# Steering_Converter_1R1.net
KiCad netlist of a schematic drawn in Altium Designer
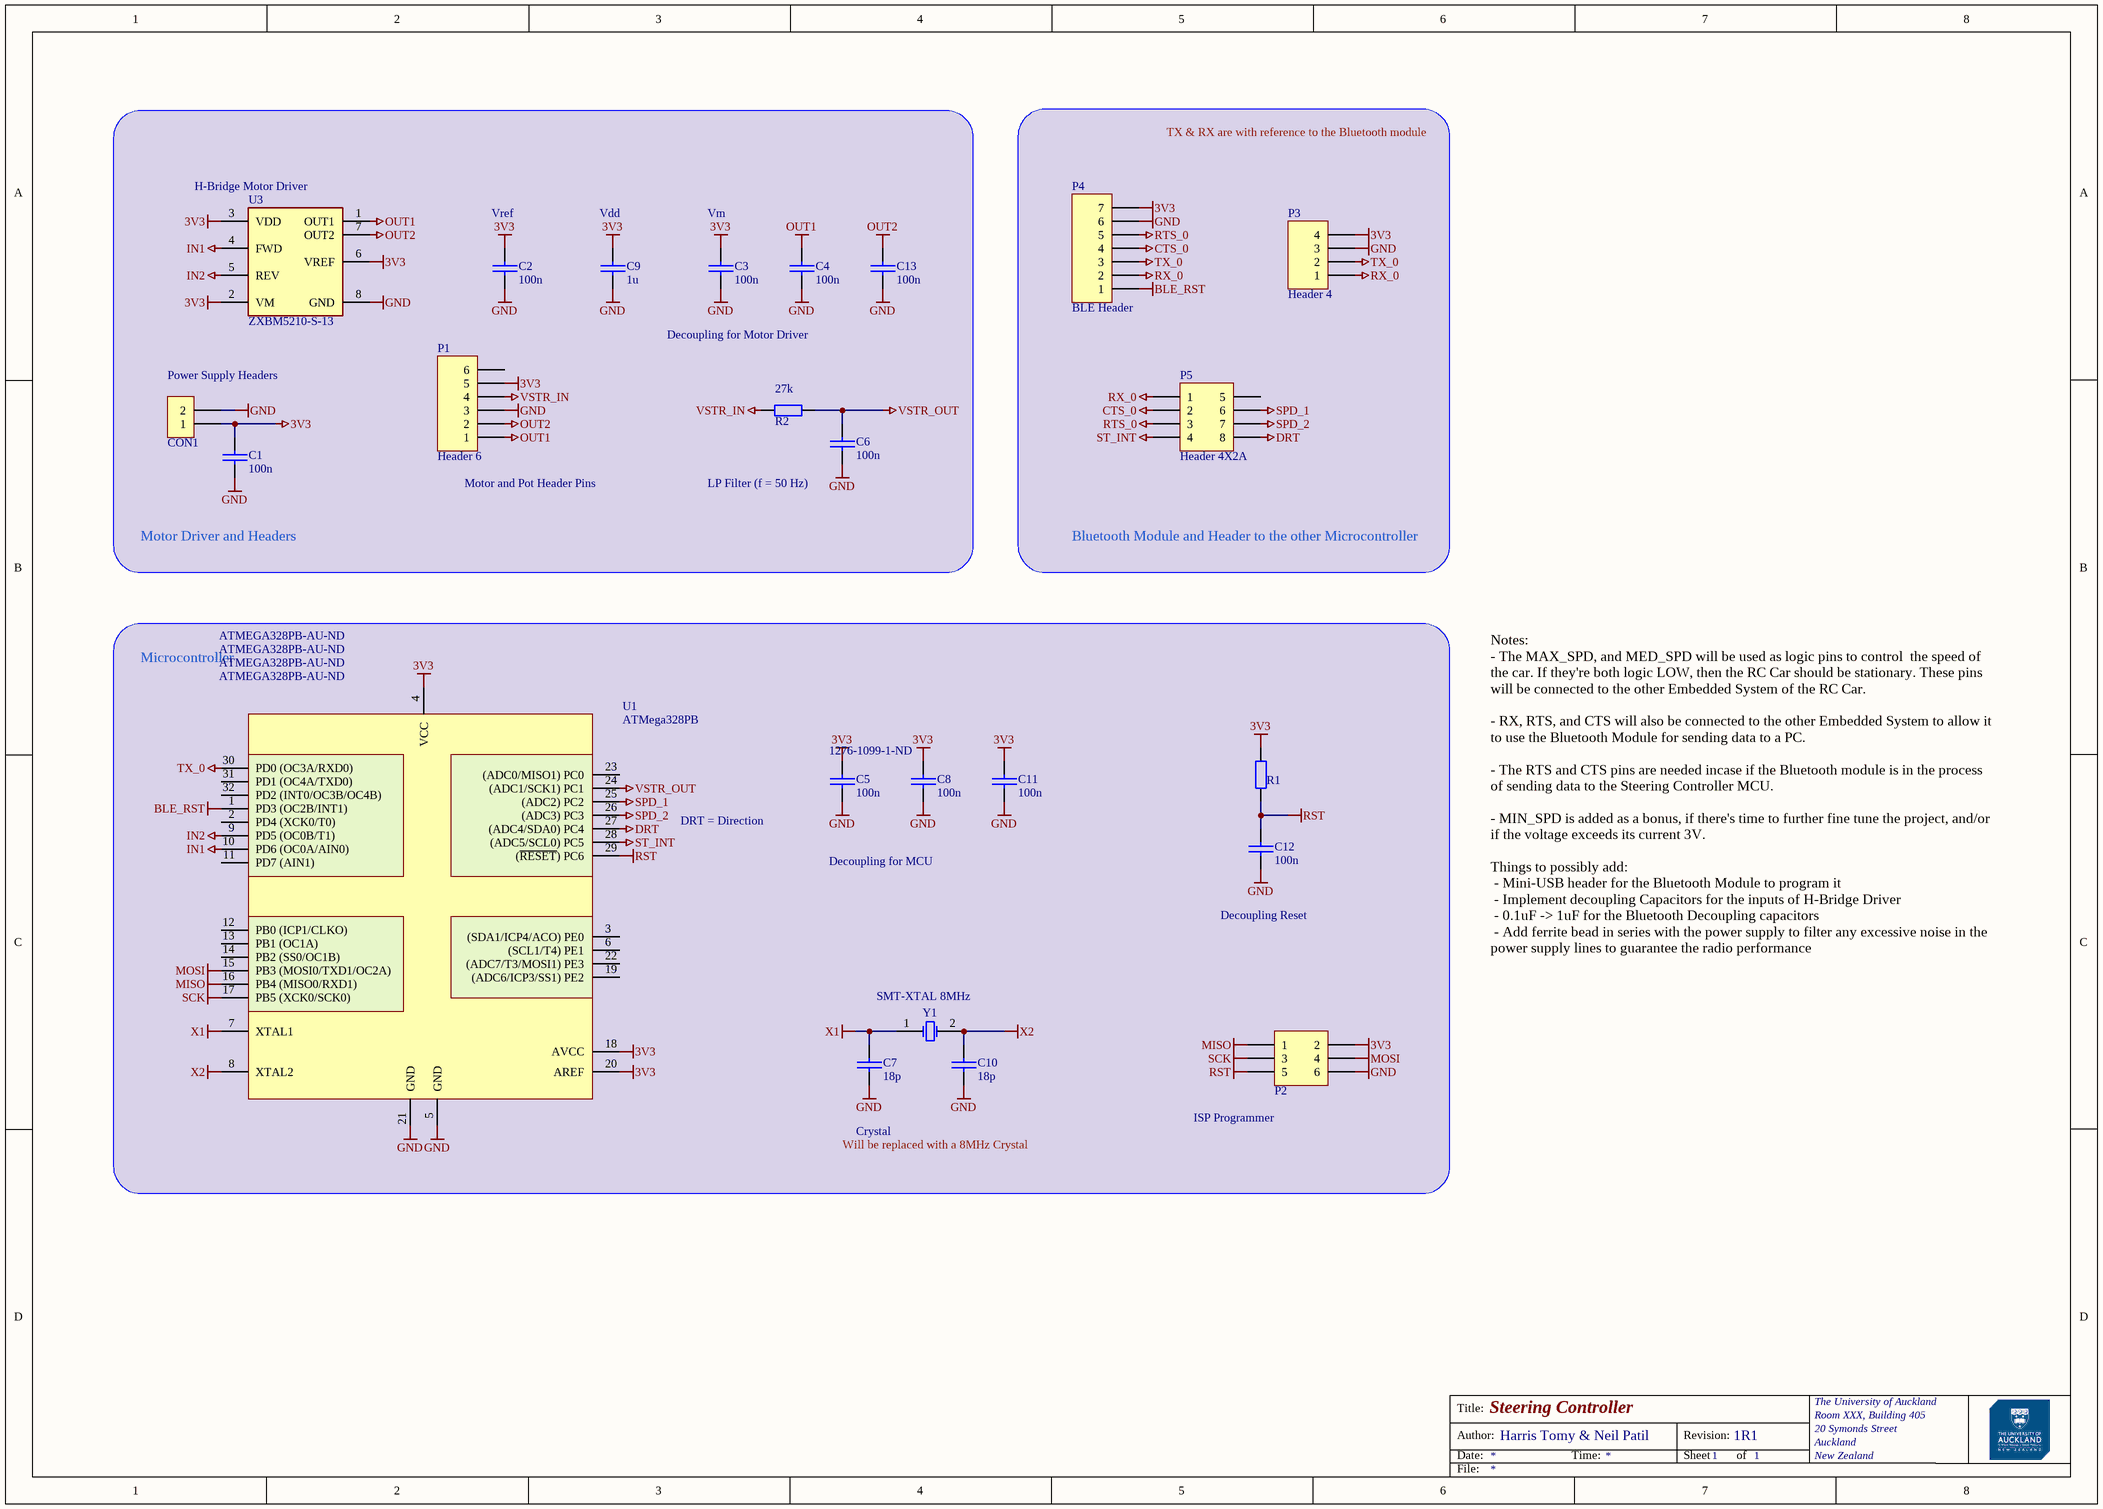
[diagram p0: Steering_Converter_1R1.SchDoc]

(export (version "E")
  (design (tool "Eeschema 10.0.6"))
  (components
    (comp (ref "C1")
      (value "100n")
      (footprint "C0805")
      (description "CCAP0805")
      (fields (field (name "MPN") "?"))
      (libsource (lib "E209_Lib") (part "CCAP0805"))
    )
    (comp (ref "C2")
      (value "100n")
      (footprint "C0805")
      (description "CCAP0805")
      (fields (field (name "MPN") "?"))
      (libsource (lib "E209_Lib") (part "CCAP0805"))
    )
    (comp (ref "C3")
      (value "100n")
      (footprint "C0805")
      (description "CCAP0805")
      (fields (field (name "MPN") "?"))
      (libsource (lib "E209_Lib") (part "CCAP0805"))
    )
    (comp (ref "C4")
      (value "100n")
      (footprint "C0805")
      (description "CCAP0805")
      (fields (field (name "MPN") "?"))
      (libsource (lib "E209_Lib") (part "CCAP0805"))
    )
    (comp (ref "C5")
      (value "100n")
      (footprint "C0805")
      (description "CCAP0805")
      (fields (field (name "MPN") "?") (field (name "SUPPLIER PART NUMBER 1") "1276-1099-1-ND"))
      (libsource (lib "E209_Lib") (part "CCAP0805"))
    )
    (comp (ref "C6")
      (value "100n")
      (footprint "C0805")
      (description "CCAP0805")
      (fields (field (name "MPN") "?"))
      (libsource (lib "E209_Lib") (part "CCAP0805"))
    )
    (comp (ref "C7")
      (value "18p")
      (footprint "C0805")
      (description "CCAP0805")
      (fields (field (name "MPN") "?"))
      (libsource (lib "E209_Lib") (part "CCAP0805"))
    )
    (comp (ref "C8")
      (value "100n")
      (footprint "C0805")
      (description "CCAP0805")
      (fields (field (name "MPN") "?"))
      (libsource (lib "E209_Lib") (part "CCAP0805"))
    )
    (comp (ref "C9")
      (value "1u")
      (footprint "C0805")
      (description "CCAP0805")
      (fields (field (name "MPN") "?"))
      (libsource (lib "E209_Lib") (part "CCAP0805"))
    )
    (comp (ref "C10")
      (value "18p")
      (footprint "C0805")
      (description "CCAP0805")
      (fields (field (name "MPN") "?"))
      (libsource (lib "E209_Lib") (part "CCAP0805"))
    )
    (comp (ref "C11")
      (value "100n")
      (footprint "C0805")
      (description "CCAP0805")
      (fields (field (name "MPN") "?"))
      (libsource (lib "E209_Lib") (part "CCAP0805"))
    )
    (comp (ref "C12")
      (value "100n")
      (footprint "C0805")
      (description "CCAP0805")
      (fields (field (name "MPN") "?"))
      (libsource (lib "E209_Lib") (part "CCAP0805"))
    )
    (comp (ref "C13")
      (value "100n")
      (footprint "C0805")
      (description "CCAP0805")
      (fields (field (name "MPN") "?"))
      (libsource (lib "E209_Lib") (part "CCAP0805"))
    )
    (comp (ref "CON1")
      (value "Header 2X1")
      (footprint "HDR2X1_2P54")
      (libsource (lib "CommonDevices_V1") (part "HDR2X1"))
    )
    (comp (ref "P1")
      (value "Header 6")
      (footprint "HDR1X6")
      (description "Header, 6-Pin")
      (fields (field (name "PUBLISHER") "Altium Limited"))
      (libsource (lib "Miscellaneous Connectors") (part "Header 6"))
    )
    (comp (ref "P2")
      (value "HDR3X2")
      (footprint "HDR2X3_2P54")
      (description "Header, 3-Pin, Dual row")
      (libsource (lib "CommonDevices_V1") (part "HDR3X2"))
    )
    (comp (ref "P3")
      (value "Header 4")
      (footprint "HDR1X4")
      (description "Header, 4-Pin")
      (fields (field (name "PUBLISHER") "Altium Limited"))
      (libsource (lib "Miscellaneous Connectors") (part "Header 4"))
    )
    (comp (ref "P4")
      (value "BLE Header")
      (footprint "HDR1X7")
      (description "Header, 7-Pin")
      (fields (field (name "PUBLISHER") "Altium Limited"))
      (libsource (lib "Miscellaneous Connectors") (part "Header 7"))
    )
    (comp (ref "P5")
      (value "Header 4X2A")
      (footprint "HDR2X4_CEN")
      (description "Header, 4-Pin, Dual row")
      (fields (field (name "PUBLISHER") "Altium Limited"))
      (libsource (lib "Miscellaneous Connectors") (part "Header 4X2A"))
    )
    (comp (ref "R1")
      (value "Resistor 0805")
      (footprint "R0805")
      (description "RES0805")
      (fields (field (name "MPN") "?"))
      (libsource (lib "E209_Lib") (part "RES0805"))
    )
    (comp (ref "R2")
      (value "Resistor 0805")
      (footprint "R0805")
      (description "RES0805")
      (fields (field (name "MPN") "?"))
      (libsource (lib "") (part "RES0805_1"))
    )
    (comp (ref "U1")
      (value "ATMega328PB")
      (footprint "TQFP32")
      (description "IC MCU 8BIT 32KB FLASH 32TQFP")
      (fields
        (field (name "SUPPLIER PART NUMBER 1") "ATMEGA328PB-AU-ND")
        (field (name "SUPPLIER PART NUMBER 2") "ATMEGA328PB-AU-ND")
        (field (name "SUPPLIER PART NUMBER 3") "ATMEGA328PB-AU-ND")
        (field (name "SUPPLIER PART NUMBER 4") "ATMEGA328PB-AU-ND")
      )
      (libsource (lib "CommonDevices_V1") (part "ATMega328PB"))
    )
    (comp (ref "U3")
      (value "IC_Diodes_ZXBM5210-S-13_eec")
      (footprint "Diodes_ZXBM5210-S-13_0")
      (description "IC MOTOR DRIVER PWM 8SOIC")
      (fields
        (field (name "PART NUMBER") "ZXBM5210-S-13")
        (field (name "VOLTAGE") "18V")
        (field (name "MANUFACTURER") "Diodes")
      )
      (libsource (lib "ZXBM5210-S-13") (part "IC_Diodes_ZXBM5210-S-13_eec"))
    )
    (comp (ref "Y1")
      (value "SMT-XTAL 8MHz")
      (footprint "HC49-US")
      (description "9C-16.000MAAJ-T crystal 16.0000MHZ 18PF SMD")
      (fields
        (field (name "MANUFACTURER") "TXC CORPORATION")
        (field (name "MANUFACTURER PART NUMBER") "9C-16.000MAAJ-T")
      )
      (libsource (lib "EE209_Library") (part "TXC9C-16_XTAL_SMT"))
    )
  )
  (nets
    (net (code "1") (name "3V3") (class "Default")
      (node (ref "C1") (pin "2") (pinfunction "2_2") (pintype "passive"))
      (node (ref "C11") (pin "2") (pinfunction "2_2") (pintype "passive"))
      (node (ref "C2") (pin "2") (pinfunction "2_2") (pintype "passive"))
      (node (ref "C3") (pin "2") (pinfunction "2_2") (pintype "passive"))
      (node (ref "C5") (pin "2") (pinfunction "2_2") (pintype "passive"))
      (node (ref "C8") (pin "2") (pinfunction "2_2") (pintype "passive"))
      (node (ref "C9") (pin "2") (pinfunction "2_2") (pintype "passive"))
      (node (ref "CON1") (pin "1") (pinfunction "1_1") (pintype "passive"))
      (node (ref "P1") (pin "5") (pinfunction "5_5") (pintype "passive"))
      (node (ref "P2") (pin "2") (pinfunction "2_2") (pintype "passive"))
      (node (ref "P3") (pin "4") (pinfunction "4_4") (pintype "passive"))
      (node (ref "P4") (pin "7") (pinfunction "7_7") (pintype "passive"))
      (node (ref "R1") (pin "2") (pinfunction "2_2") (pintype "passive"))
      (node (ref "U1") (pin "18") (pinfunction "AVCC_18") (pintype "passive"))
      (node (ref "U1") (pin "20") (pinfunction "AREF_20") (pintype "passive"))
      (node (ref "U1") (pin "4") (pinfunction "VCC_4") (pintype "passive"))
      (node (ref "U3") (pin "2") (pinfunction "VM_2") (pintype "passive"))
      (node (ref "U3") (pin "3") (pinfunction "VDD_3") (pintype "passive"))
      (node (ref "U3") (pin "6") (pinfunction "VREF_6") (pintype "passive"))
    )
    (net (code "2") (name "BLE_RST") (class "Default")
      (node (ref "P4") (pin "1") (pinfunction "1_1") (pintype "passive"))
      (node (ref "U1") (pin "1") (pinfunction "PD3_(OC2B/INT1)_1") (pintype "passive"))
    )
    (net (code "3") (name "CTS_0") (class "Default")
      (node (ref "P4") (pin "4") (pinfunction "4_4") (pintype "passive"))
      (node (ref "P5") (pin "2") (pinfunction "2_2") (pintype "passive"))
    )
    (net (code "4") (name "DRT") (class "Default")
      (node (ref "P5") (pin "8") (pinfunction "8_8") (pintype "passive"))
      (node (ref "U1") (pin "27") (pinfunction "(ADC4/SDA0)_PC4_27") (pintype "passive"))
    )
    (net (code "5") (name "GND") (class "Default")
      (node (ref "C1") (pin "1") (pinfunction "1_1") (pintype "passive"))
      (node (ref "C10") (pin "1") (pinfunction "1_1") (pintype "passive"))
      (node (ref "C11") (pin "1") (pinfunction "1_1") (pintype "passive"))
      (node (ref "C12") (pin "1") (pinfunction "1_1") (pintype "passive"))
      (node (ref "C13") (pin "1") (pinfunction "1_1") (pintype "passive"))
      (node (ref "C2") (pin "1") (pinfunction "1_1") (pintype "passive"))
      (node (ref "C3") (pin "1") (pinfunction "1_1") (pintype "passive"))
      (node (ref "C4") (pin "1") (pinfunction "1_1") (pintype "passive"))
      (node (ref "C5") (pin "1") (pinfunction "1_1") (pintype "passive"))
      (node (ref "C6") (pin "1") (pinfunction "1_1") (pintype "passive"))
      (node (ref "C7") (pin "1") (pinfunction "1_1") (pintype "passive"))
      (node (ref "C8") (pin "1") (pinfunction "1_1") (pintype "passive"))
      (node (ref "C9") (pin "1") (pinfunction "1_1") (pintype "passive"))
      (node (ref "CON1") (pin "2") (pinfunction "2_2") (pintype "passive"))
      (node (ref "P1") (pin "3") (pinfunction "3_3") (pintype "passive"))
      (node (ref "P2") (pin "6") (pinfunction "6_6") (pintype "passive"))
      (node (ref "P3") (pin "3") (pinfunction "3_3") (pintype "passive"))
      (node (ref "P4") (pin "6") (pinfunction "6_6") (pintype "passive"))
      (node (ref "U1") (pin "21") (pinfunction "GND_21") (pintype "passive"))
      (node (ref "U1") (pin "5") (pinfunction "GND_5") (pintype "passive"))
      (node (ref "U3") (pin "8") (pinfunction "GND_8") (pintype "passive"))
    )
    (net (code "6") (name "IN1") (class "Default")
      (node (ref "U1") (pin "10") (pinfunction "PD6_(OC0A/AIN0)_10") (pintype "passive"))
      (node (ref "U3") (pin "4") (pinfunction "FWD_4") (pintype "passive"))
    )
    (net (code "7") (name "IN2") (class "Default")
      (node (ref "U1") (pin "9") (pinfunction "PD5_(OC0B/T1)_9") (pintype "passive"))
      (node (ref "U3") (pin "5") (pinfunction "REV_5") (pintype "passive"))
    )
    (net (code "8") (name "MISO") (class "Default")
      (node (ref "P2") (pin "1") (pinfunction "1_1") (pintype "passive"))
      (node (ref "U1") (pin "16") (pinfunction "PB4_(MISO0/RXD1)_16") (pintype "passive"))
    )
    (net (code "9") (name "MOSI") (class "Default")
      (node (ref "P2") (pin "4") (pinfunction "4_4") (pintype "passive"))
      (node (ref "U1") (pin "15") (pinfunction "PB3_(MOSI0/TXD1/OC2A)_15") (pintype "passive"))
    )
    (net (code "10") (name "OUT1") (class "Default")
      (node (ref "C4") (pin "2") (pinfunction "2_2") (pintype "passive"))
      (node (ref "P1") (pin "1") (pinfunction "1_1") (pintype "passive"))
      (node (ref "U3") (pin "1") (pinfunction "OUT1_1") (pintype "passive"))
    )
    (net (code "11") (name "OUT2") (class "Default")
      (node (ref "C13") (pin "2") (pinfunction "2_2") (pintype "passive"))
      (node (ref "P1") (pin "2") (pinfunction "2_2") (pintype "passive"))
      (node (ref "U3") (pin "7") (pinfunction "OUT2_7") (pintype "passive"))
    )
    (net (code "12") (name "RST") (class "Default")
      (node (ref "C12") (pin "2") (pinfunction "2_2") (pintype "passive"))
      (node (ref "P2") (pin "5") (pinfunction "5_5") (pintype "passive"))
      (node (ref "R1") (pin "1") (pinfunction "1_1") (pintype "passive"))
      (node (ref "U1") (pin "29") (pinfunction "(~{RESET})_PC6_29") (pintype "passive"))
    )
    (net (code "13") (name "RTS_0") (class "Default")
      (node (ref "P4") (pin "5") (pinfunction "5_5") (pintype "passive"))
      (node (ref "P5") (pin "3") (pinfunction "3_3") (pintype "passive"))
    )
    (net (code "14") (name "RX_0") (class "Default")
      (node (ref "P3") (pin "1") (pinfunction "1_1") (pintype "passive"))
      (node (ref "P4") (pin "2") (pinfunction "2_2") (pintype "passive"))
      (node (ref "P5") (pin "1") (pinfunction "1_1") (pintype "passive"))
    )
    (net (code "15") (name "SCK") (class "Default")
      (node (ref "P2") (pin "3") (pinfunction "3_3") (pintype "passive"))
      (node (ref "U1") (pin "17") (pinfunction "PB5_(XCK0/SCK0)_17") (pintype "passive"))
    )
    (net (code "16") (name "SPD_1") (class "Default")
      (node (ref "P5") (pin "6") (pinfunction "6_6") (pintype "passive"))
      (node (ref "U1") (pin "25") (pinfunction "(ADC2)_PC2_25") (pintype "passive"))
    )
    (net (code "17") (name "SPD_2") (class "Default")
      (node (ref "P5") (pin "7") (pinfunction "7_7") (pintype "passive"))
      (node (ref "U1") (pin "26") (pinfunction "(ADC3)_PC3_26") (pintype "passive"))
    )
    (net (code "18") (name "ST_INT") (class "Default")
      (node (ref "P5") (pin "4") (pinfunction "4_4") (pintype "passive"))
      (node (ref "U1") (pin "28") (pinfunction "(ADC5/SCL0)_PC5_28") (pintype "passive"))
    )
    (net (code "19") (name "TX_0") (class "Default")
      (node (ref "P3") (pin "2") (pinfunction "2_2") (pintype "passive"))
      (node (ref "P4") (pin "3") (pinfunction "3_3") (pintype "passive"))
      (node (ref "U1") (pin "30") (pinfunction "PD0_(OC3A/RXD0)_30") (pintype "passive"))
    )
    (net (code "20") (name "VSTR_IN") (class "Default")
      (node (ref "P1") (pin "4") (pinfunction "4_4") (pintype "passive"))
      (node (ref "R2") (pin "1") (pinfunction "1_1") (pintype "passive"))
    )
    (net (code "21") (name "VSTR_OUT") (class "Default")
      (node (ref "C6") (pin "2") (pinfunction "2_2") (pintype "passive"))
      (node (ref "R2") (pin "2") (pinfunction "2_2") (pintype "passive"))
      (node (ref "U1") (pin "24") (pinfunction "(ADC1/SCK1)_PC1_24") (pintype "passive"))
    )
    (net (code "22") (name "X1") (class "Default")
      (node (ref "C7") (pin "2") (pinfunction "2_2") (pintype "passive"))
      (node (ref "U1") (pin "7") (pinfunction "XTAL1_7") (pintype "passive"))
      (node (ref "Y1") (pin "1") (pinfunction "OSC1_1") (pintype "passive"))
    )
    (net (code "23") (name "X2") (class "Default")
      (node (ref "C10") (pin "2") (pinfunction "2_2") (pintype "passive"))
      (node (ref "U1") (pin "8") (pinfunction "XTAL2_8") (pintype "passive"))
      (node (ref "Y1") (pin "2") (pinfunction "OSC2_2") (pintype "passive"))
    )
    (net (code "24") (name "unconnected-(P1-Pad6)") (class "Default")
      (node (ref "P1") (pin "6") (pinfunction "6_6") (pintype "passive"))
    )
    (net (code "25") (name "unconnected-(P5-Pad5)") (class "Default")
      (node (ref "P5") (pin "5") (pinfunction "5_5") (pintype "passive"))
    )
    (net (code "26") (name "unconnected-(U1-(ADC0{slash}MISO1)_PC0-Pad23)") (class "Default")
      (node (ref "U1") (pin "23") (pinfunction "(ADC0/MISO1)_PC0_23") (pintype "passive"))
    )
    (net (code "27") (name "unconnected-(U1-(ADC6{slash}ICP3{slash}SS1)_PE2-Pad19)") (class "Default")
      (node (ref "U1") (pin "19") (pinfunction "(ADC6/ICP3/SS1)_PE2_19") (pintype "passive"))
    )
    (net (code "28") (name "unconnected-(U1-(ADC7{slash}T3{slash}MOSI1)_PE3-Pad22)") (class "Default")
      (node (ref "U1") (pin "22") (pinfunction "(ADC7/T3/MOSI1)_PE3_22") (pintype "passive"))
    )
    (net (code "29") (name "unconnected-(U1-(SCL1{slash}T4)_PE1-Pad6)") (class "Default")
      (node (ref "U1") (pin "6") (pinfunction "(SCL1/T4)_PE1_6") (pintype "passive"))
    )
    (net (code "30") (name "unconnected-(U1-(SDA1{slash}ICP4{slash}ACO)_PE0-Pad3)") (class "Default")
      (node (ref "U1") (pin "3") (pinfunction "(SDA1/ICP4/ACO)_PE0_3") (pintype "passive"))
    )
    (net (code "31") (name "unconnected-(U1-PB0_(ICP1{slash}CLKO)-Pad12)") (class "Default")
      (node (ref "U1") (pin "12") (pinfunction "PB0_(ICP1/CLKO)_12") (pintype "passive"))
    )
    (net (code "32") (name "unconnected-(U1-PB1_(OC1A)-Pad13)") (class "Default")
      (node (ref "U1") (pin "13") (pinfunction "PB1_(OC1A)_13") (pintype "passive"))
    )
    (net (code "33") (name "unconnected-(U1-PB2_(SS0{slash}OC1B)-Pad14)") (class "Default")
      (node (ref "U1") (pin "14") (pinfunction "PB2_(SS0/OC1B)_14") (pintype "passive"))
    )
    (net (code "34") (name "unconnected-(U1-PD1_(OC4A{slash}TXD0)-Pad31)") (class "Default")
      (node (ref "U1") (pin "31") (pinfunction "PD1_(OC4A/TXD0)_31") (pintype "passive"))
    )
    (net (code "35") (name "unconnected-(U1-PD2_(INT0{slash}OC3B{slash}OC4B)-Pad32)") (class "Default")
      (node (ref "U1") (pin "32") (pinfunction "PD2_(INT0/OC3B/OC4B)_32") (pintype "passive"))
    )
    (net (code "36") (name "unconnected-(U1-PD4_(XCK0{slash}T0)-Pad2)") (class "Default")
      (node (ref "U1") (pin "2") (pinfunction "PD4_(XCK0/T0)_2") (pintype "passive"))
    )
    (net (code "37") (name "unconnected-(U1-PD7_(AIN1)-Pad11)") (class "Default")
      (node (ref "U1") (pin "11") (pinfunction "PD7_(AIN1)_11") (pintype "passive"))
    )
  )
)
